# AMU-S05-V00-CANMAIN.net
KiCad netlist of a schematic drawn in Altium Designer
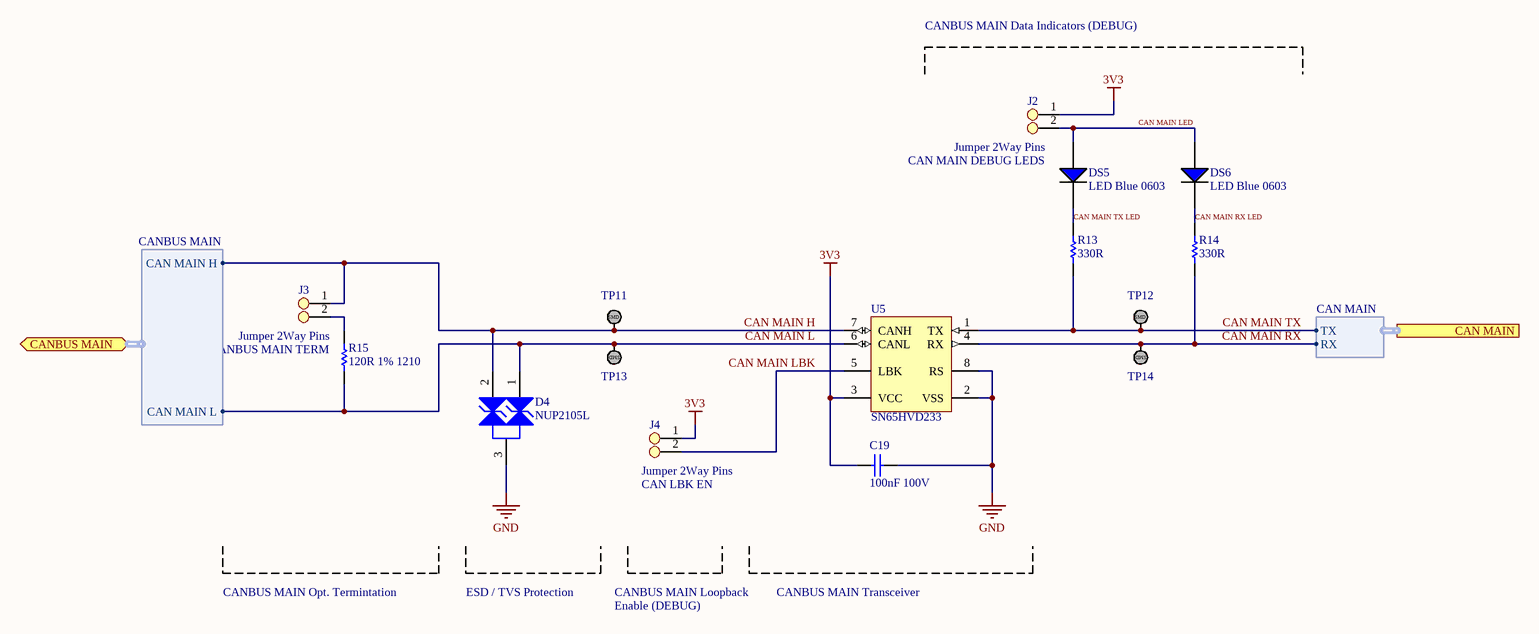
[diagram p0: AMU-S05-V00-CANMAIN.SchDoc]

(export (version "E")
  (design (tool "Eeschema 10.0.6"))
  (components
    (comp (ref "C19")
      (value "100nF 100V")
      (footprint "Cap_Ceramic_0603")
      (description "Capacitor, Ceramic, SMD, 100nF, 100V, 5%, X7R, 0603")
      (libsource (lib "StandardCapacitors") (part "100nF 100V 5% X7R 0603"))
    )
    (comp (ref "D4")
      (value "NUP2105L")
      (footprint "NUP2105L")
      (libsource (lib "QUTMS_CANLibrary") (part "NUP2105L"))
    )
    (comp (ref "DS5")
      (value "LED Blue 0603")
      (footprint "LED BLUE 0603")
      (libsource (lib "QUTMS_LEDLibrary") (part "LED BLUE 0603"))
    )
    (comp (ref "DS6")
      (value "LED Blue 0603")
      (footprint "LED BLUE 0603")
      (libsource (lib "QUTMS_LEDLibrary") (part "LED BLUE 0603"))
    )
    (comp (ref "J2")
      (value "Jumper 2Way Pins")
      (footprint "Jumper_2Way_Pin")
      (description "Jumper 2Way Side Pins")
      (libsource (lib "QUTMS_JumperLibrary") (part "Jumper 2Way Side Pins"))
    )
    (comp (ref "J3")
      (value "Jumper 2Way Pins")
      (footprint "Jumper_2Way_Pin")
      (description "Jumper 2Way Side Pins")
      (libsource (lib "QUTMS_JumperLibrary") (part "Jumper 2Way Side Pins"))
    )
    (comp (ref "J4")
      (value "Jumper 2Way Pins")
      (footprint "Jumper_2Way_Pin")
      (description "Jumper 2Way Side Pins")
      (libsource (lib "QUTMS_JumperLibrary") (part "Jumper 2Way Side Pins"))
    )
    (comp (ref "R13")
      (value "330R")
      (footprint "Res_ThinFilm_0603")
      (description "Resistor, SMD, 330R, 0.1W, 5%, 0603")
      (libsource (lib "StandardResistors") (part "330R 5% 0603"))
    )
    (comp (ref "R14")
      (value "330R")
      (footprint "Res_ThinFilm_0603")
      (description "Resistor, SMD, 330R, 0.1W, 5%, 0603")
      (libsource (lib "StandardResistors") (part "330R 5% 0603"))
    )
    (comp (ref "R15")
      (value "120R 1% 1210")
      (footprint "Res_ThinFilm_1210")
      (description "Resistor, SMD, 120R, 0.25W, 1%, 1210")
      (libsource (lib "StandardResistors") (part "120R 1% 1210"))
    )
    (comp (ref "TP11")
      (value "TestPoint_SMD")
      (footprint "TestPointSMD")
      (libsource (lib "StandardTest") (part "TestPoint_SMD"))
    )
    (comp (ref "TP12")
      (value "TestPoint_SMD")
      (footprint "TestPointSMD")
      (libsource (lib "StandardTest") (part "TestPoint_SMD"))
    )
    (comp (ref "TP13")
      (value "TestPoint_SMD")
      (footprint "TestPointSMD")
      (libsource (lib "StandardTest") (part "TestPoint_SMD"))
    )
    (comp (ref "TP14")
      (value "TestPoint_SMD")
      (footprint "TestPointSMD")
      (libsource (lib "StandardTest") (part "TestPoint_SMD"))
    )
    (comp (ref "U5")
      (value "SN65HVD233")
      (footprint "SN65HVD233DR")
      (libsource (lib "QUTMS_CANLibrary") (part "SN65HVD233"))
    )
  )
  (nets
    (net (code "4") (name "/CAN MAIN H") (class "Default")
      (node (ref "D4") (pin "2") (pinfunction "2_2") (pintype "passive"))
      (node (ref "J3") (pin "1") (pinfunction "1_1") (pintype "passive"))
      (node (ref "TP11") (pin "1") (pinfunction "1_1") (pintype "passive"))
      (node (ref "U5") (pin "7") (pinfunction "CANH_7") (pintype "bidirectional"))
    )
    (net (code "5") (name "/CAN MAIN L") (class "Default")
      (node (ref "D4") (pin "1") (pinfunction "1_1") (pintype "passive"))
      (node (ref "R15") (pin "1") (pinfunction "1_1") (pintype "passive"))
      (node (ref "TP13") (pin "1") (pinfunction "1_1") (pintype "passive"))
      (node (ref "U5") (pin "6") (pinfunction "CANL_6") (pintype "bidirectional"))
    )
    (net (code "6") (name "/CAN MAIN LBK") (class "Default")
      (node (ref "J4") (pin "2") (pinfunction "2_2") (pintype "passive"))
      (node (ref "U5") (pin "5") (pinfunction "LBK_5") (pintype "passive"))
    )
    (net (code "7") (name "/CAN MAIN LED") (class "Default")
      (node (ref "DS5") (pin "1") (pinfunction "A_1") (pintype "passive"))
      (node (ref "DS6") (pin "1") (pinfunction "A_1") (pintype "passive"))
      (node (ref "J2") (pin "2") (pinfunction "2_2") (pintype "passive"))
    )
    (net (code "8") (name "/CAN MAIN RX") (class "Default")
      (node (ref "R14") (pin "1") (pinfunction "1_1") (pintype "passive"))
      (node (ref "TP14") (pin "1") (pinfunction "1_1") (pintype "passive"))
      (node (ref "U5") (pin "4") (pinfunction "RX_4") (pintype "output"))
    )
    (net (code "9") (name "/CAN MAIN RX LED") (class "Default")
      (node (ref "DS6") (pin "2") (pinfunction "C_2") (pintype "passive"))
      (node (ref "R14") (pin "2") (pinfunction "2_2") (pintype "passive"))
    )
    (net (code "10") (name "/CAN MAIN TX") (class "Default")
      (node (ref "R13") (pin "1") (pinfunction "1_1") (pintype "passive"))
      (node (ref "TP12") (pin "1") (pinfunction "1_1") (pintype "passive"))
      (node (ref "U5") (pin "1") (pinfunction "TX_1") (pintype "input"))
    )
    (net (code "11") (name "/CAN MAIN TX LED") (class "Default")
      (node (ref "DS5") (pin "2") (pinfunction "C_2") (pintype "passive"))
      (node (ref "R13") (pin "2") (pinfunction "2_2") (pintype "passive"))
    )
    (net (code "14") (name "3V3") (class "Default")
      (node (ref "C19") (pin "2") (pinfunction "2_2") (pintype "passive"))
      (node (ref "J2") (pin "1") (pinfunction "1_1") (pintype "passive"))
      (node (ref "J4") (pin "1") (pinfunction "1_1") (pintype "passive"))
      (node (ref "U5") (pin "3") (pinfunction "VCC_3") (pintype "passive"))
    )
    (net (code "15") (name "GND") (class "Default")
      (node (ref "C19") (pin "1") (pinfunction "1_1") (pintype "passive"))
      (node (ref "D4") (pin "3") (pinfunction "3_3") (pintype "passive"))
      (node (ref "U5") (pin "2") (pinfunction "VSS_2") (pintype "passive"))
      (node (ref "U5") (pin "8") (pinfunction "RS_8") (pintype "passive"))
    )
    (net (code "16") (name "Net-(J3-Pad2)") (class "Default")
      (node (ref "J3") (pin "2") (pinfunction "2_2") (pintype "passive"))
      (node (ref "R15") (pin "2") (pinfunction "2_2") (pintype "passive"))
    )
  )
)
